# MiniMoto_--_BREAKOUT.net
KiCad netlist of a schematic drawn in EAGLE
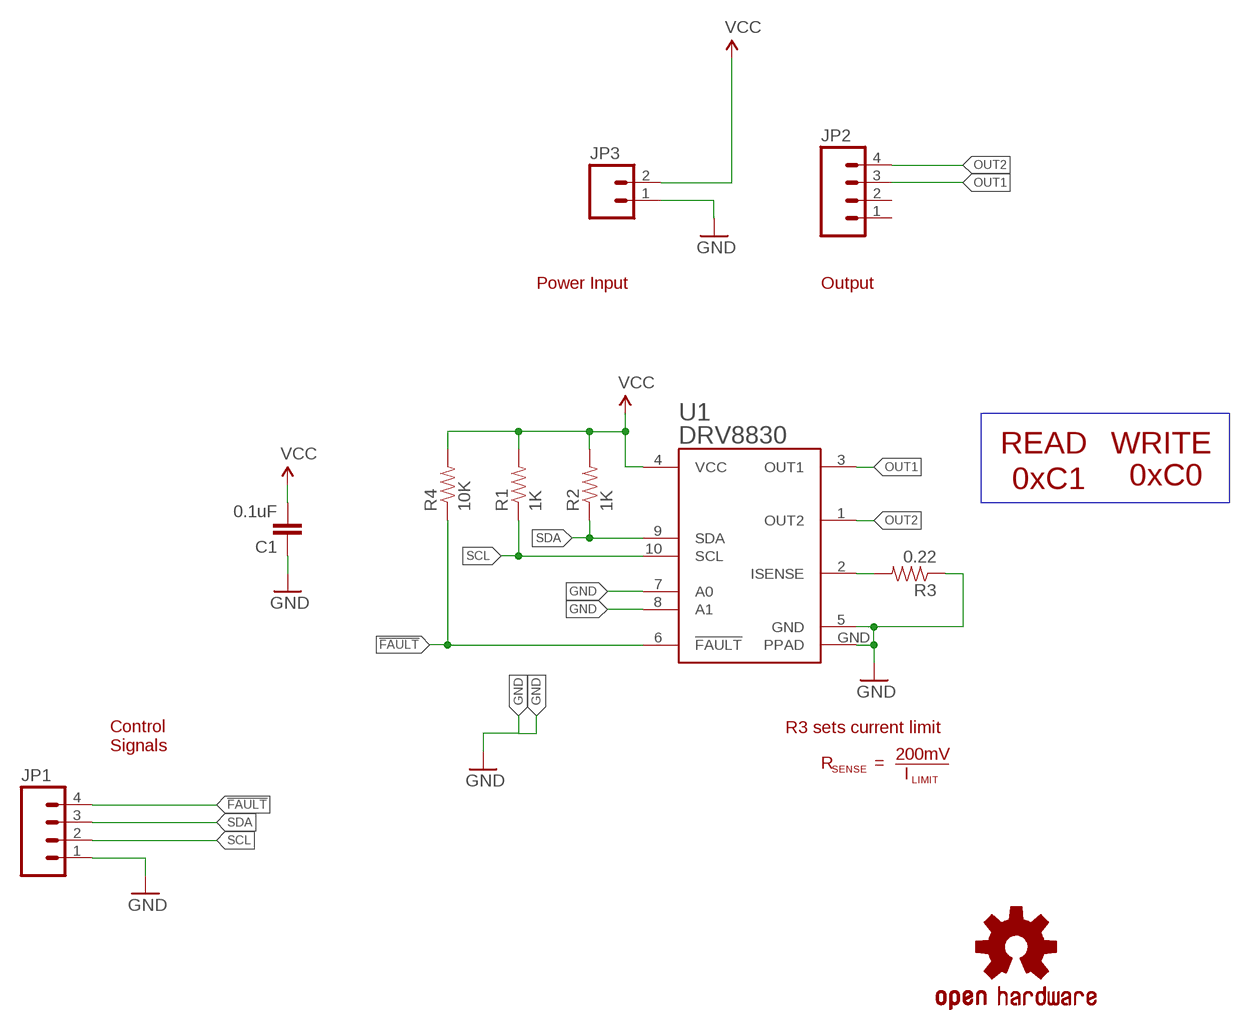
[diagram p0: schematic, sheet 1]

(export (version "E")
  (design (tool "Eeschema 10.0.6"))
  (components
    (comp (ref "C1")
      (value "0.1uF")
      (footprint "eagle-import:0603-CAP")
      (libsource (lib "eagle-import") (part "0.1UF-25V(+80/-20%)(0603)"))
    )
    (comp (ref "JP1")
      (value "M04PTH")
      (footprint "eagle-import:1X04")
      (libsource (lib "eagle-import") (part "M04PTH"))
    )
    (comp (ref "JP2")
      (value "M04PTH")
      (footprint "eagle-import:1X04")
      (libsource (lib "eagle-import") (part "M04PTH"))
    )
    (comp (ref "JP3")
      (value "M02LOCK")
      (footprint "eagle-import:1X02_LOCK")
      (libsource (lib "eagle-import") (part "M02LOCK"))
    )
    (comp (ref "LOGO3")
      (value "OSHW-LOGOS")
      (footprint "eagle-import:OSHW-LOGO-S")
      (libsource (lib "eagle-import") (part "OSHW-LOGOS"))
    )
    (comp (ref "R1")
      (value "1K")
      (footprint "eagle-import:0603-RES")
      (libsource (lib "eagle-import") (part "1KOHM1/10W1%(0603)"))
    )
    (comp (ref "R2")
      (value "1K")
      (footprint "eagle-import:0603-RES")
      (libsource (lib "eagle-import") (part "1KOHM1/10W1%(0603)"))
    )
    (comp (ref "R3")
      (value "0.22")
      (footprint "eagle-import:0805")
      (libsource (lib "eagle-import") (part "0.22OHM1/4W1%(0805)"))
    )
    (comp (ref "R4")
      (value "10K")
      (footprint "eagle-import:0603-RES")
      (libsource (lib "eagle-import") (part "10KOHM1/10W1%(0603)0603"))
    )
    (comp (ref "U1")
      (value "DRV8830")
      (footprint "eagle-import:MSOP-10-GNDPAD")
      (libsource (lib "eagle-import") (part "DRV8830"))
    )
  )
  (nets
    (net (code "1") (name "/~{FAULT}") (class "Default")
      (node (ref "JP1") (pin "4") (pinfunction "4_4") (pintype "passive"))
      (node (ref "R4") (pin "1") (pinfunction "1_1") (pintype "passive"))
      (node (ref "U1") (pin "6") (pinfunction "~{FAULT}_6") (pintype "bidirectional"))
    )
    (net (code "2") (name "GND") (class "Default")
      (node (ref "C1") (pin "1") (pinfunction "1_1") (pintype "passive"))
      (node (ref "JP1") (pin "1") (pinfunction "1_1") (pintype "passive"))
      (node (ref "JP3") (pin "1") (pinfunction "1_1") (pintype "passive"))
      (node (ref "R3") (pin "1") (pinfunction "1_1") (pintype "passive"))
      (node (ref "U1") (pin "5") (pinfunction "GND_5") (pintype "bidirectional"))
      (node (ref "U1") (pin "7") (pinfunction "A0_7") (pintype "bidirectional"))
      (node (ref "U1") (pin "8") (pinfunction "A1_8") (pintype "bidirectional"))
      (node (ref "U1") (pin "GND") (pinfunction "PPAD_GND") (pintype "bidirectional"))
    )
    (net (code "3") (name "Net-(U1-ISENSE)") (class "Default")
      (node (ref "R3") (pin "2") (pinfunction "2_2") (pintype "passive"))
      (node (ref "U1") (pin "2") (pinfunction "ISENSE_2") (pintype "bidirectional"))
    )
    (net (code "4") (name "OUT1") (class "Default")
      (node (ref "JP2") (pin "3") (pinfunction "3_3") (pintype "passive"))
      (node (ref "U1") (pin "3") (pinfunction "OUT1_3") (pintype "bidirectional"))
    )
    (net (code "5") (name "OUT2") (class "Default")
      (node (ref "JP2") (pin "4") (pinfunction "4_4") (pintype "passive"))
      (node (ref "U1") (pin "1") (pinfunction "OUT2_1") (pintype "bidirectional"))
    )
    (net (code "6") (name "SCL") (class "Default")
      (node (ref "JP1") (pin "2") (pinfunction "2_2") (pintype "passive"))
      (node (ref "R1") (pin "1") (pinfunction "1_1") (pintype "passive"))
      (node (ref "U1") (pin "10") (pinfunction "SCL_10") (pintype "bidirectional"))
    )
    (net (code "7") (name "SDA") (class "Default")
      (node (ref "JP1") (pin "3") (pinfunction "3_3") (pintype "passive"))
      (node (ref "R2") (pin "1") (pinfunction "1_1") (pintype "passive"))
      (node (ref "U1") (pin "9") (pinfunction "SDA_9") (pintype "bidirectional"))
    )
    (net (code "8") (name "VCC") (class "Default")
      (node (ref "C1") (pin "2") (pinfunction "2_2") (pintype "passive"))
      (node (ref "JP3") (pin "2") (pinfunction "2_2") (pintype "passive"))
      (node (ref "R1") (pin "2") (pinfunction "2_2") (pintype "passive"))
      (node (ref "R2") (pin "2") (pinfunction "2_2") (pintype "passive"))
      (node (ref "R4") (pin "2") (pinfunction "2_2") (pintype "passive"))
      (node (ref "U1") (pin "4") (pinfunction "VCC_4") (pintype "bidirectional"))
    )
    (net (code "9") (name "unconnected-(JP2-Pad1)") (class "Default")
      (node (ref "JP2") (pin "1") (pinfunction "1_1") (pintype "passive"))
    )
    (net (code "10") (name "unconnected-(JP2-Pad2)") (class "Default")
      (node (ref "JP2") (pin "2") (pinfunction "2_2") (pintype "passive"))
    )
  )
)
